# B204X.net
KiCad netlist of a schematic drawn in EAGLE
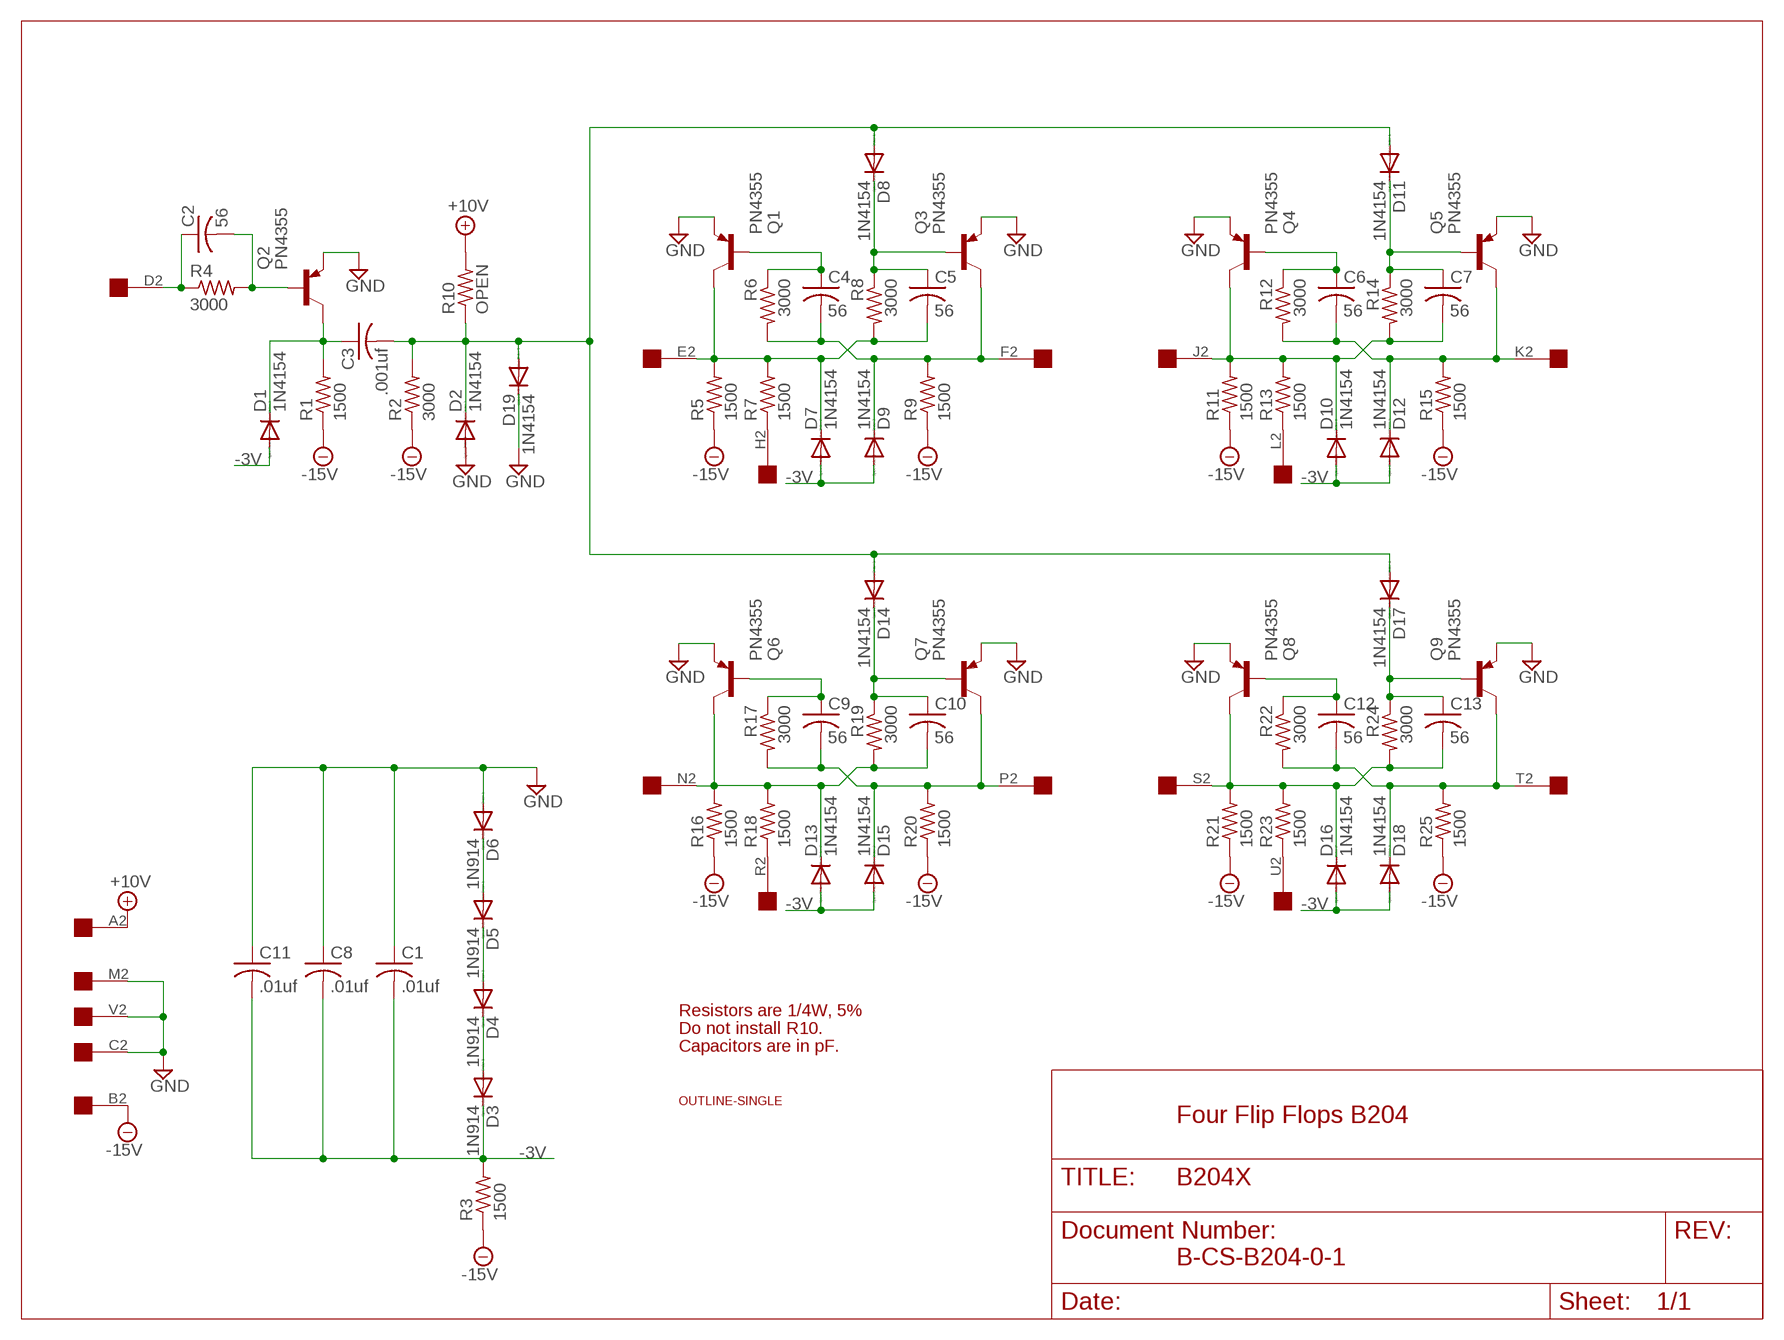
[diagram p0: schematic, sheet 1]

(export (version "E")
  (design (tool "Eeschema 10.0.6"))
  (components
    (comp (ref "C1")
      (value ".01uf")
      (footprint "eagle-import:C050-025X075")
      (libsource (lib "eagle-import") (part "C-US050-025X075"))
    )
    (comp (ref "C2")
      (value "56")
      (footprint "eagle-import:C075-032X103")
      (libsource (lib "eagle-import") (part "C-US075-032X103"))
    )
    (comp (ref "C3")
      (value ".001uf")
      (footprint "eagle-import:C050-025X075")
      (libsource (lib "eagle-import") (part "C-US050-025X075"))
    )
    (comp (ref "C4")
      (value "56")
      (footprint "eagle-import:C075-032X103")
      (libsource (lib "eagle-import") (part "C-US075-032X103"))
    )
    (comp (ref "C5")
      (value "56")
      (footprint "eagle-import:C075-032X103")
      (libsource (lib "eagle-import") (part "C-US075-032X103"))
    )
    (comp (ref "C6")
      (value "56")
      (footprint "eagle-import:C075-032X103")
      (libsource (lib "eagle-import") (part "C-US075-032X103"))
    )
    (comp (ref "C7")
      (value "56")
      (footprint "eagle-import:C075-032X103")
      (libsource (lib "eagle-import") (part "C-US075-032X103"))
    )
    (comp (ref "C8")
      (value ".01uf")
      (footprint "eagle-import:C050-025X075")
      (libsource (lib "eagle-import") (part "C-US050-025X075"))
    )
    (comp (ref "C9")
      (value "56")
      (footprint "eagle-import:C075-032X103")
      (libsource (lib "eagle-import") (part "C-US075-032X103"))
    )
    (comp (ref "C10")
      (value "56")
      (footprint "eagle-import:C075-032X103")
      (libsource (lib "eagle-import") (part "C-US075-032X103"))
    )
    (comp (ref "C11")
      (value ".01uf")
      (footprint "eagle-import:C050-025X075")
      (libsource (lib "eagle-import") (part "C-US050-025X075"))
    )
    (comp (ref "C12")
      (value "56")
      (footprint "eagle-import:C075-032X103")
      (libsource (lib "eagle-import") (part "C-US075-032X103"))
    )
    (comp (ref "C13")
      (value "56")
      (footprint "eagle-import:C075-032X103")
      (libsource (lib "eagle-import") (part "C-US075-032X103"))
    )
    (comp (ref "D1")
      (value "1N4154")
      (footprint "eagle-import:DO35-10")
      (libsource (lib "eagle-import") (part "1N4148DO35-10"))
    )
    (comp (ref "D2")
      (value "1N4154")
      (footprint "eagle-import:DO35-10")
      (libsource (lib "eagle-import") (part "1N4148DO35-10"))
    )
    (comp (ref "D3")
      (value "1N914")
      (footprint "eagle-import:DO35-10")
      (libsource (lib "eagle-import") (part "1N4148DO35-10"))
    )
    (comp (ref "D4")
      (value "1N914")
      (footprint "eagle-import:DO35-10")
      (libsource (lib "eagle-import") (part "1N4148DO35-10"))
    )
    (comp (ref "D5")
      (value "1N914")
      (footprint "eagle-import:DO35-10")
      (libsource (lib "eagle-import") (part "1N4148DO35-10"))
    )
    (comp (ref "D6")
      (value "1N914")
      (footprint "eagle-import:DO35-10")
      (libsource (lib "eagle-import") (part "1N4148DO35-10"))
    )
    (comp (ref "D7")
      (value "1N4154")
      (footprint "eagle-import:DO35-10")
      (libsource (lib "eagle-import") (part "1N4148DO35-10"))
    )
    (comp (ref "D8")
      (value "1N4154")
      (footprint "eagle-import:DO35-10")
      (libsource (lib "eagle-import") (part "1N4148DO35-10"))
    )
    (comp (ref "D9")
      (value "1N4154")
      (footprint "eagle-import:DO35-10")
      (libsource (lib "eagle-import") (part "1N4148DO35-10"))
    )
    (comp (ref "D10")
      (value "1N4154")
      (footprint "eagle-import:DO35-10")
      (libsource (lib "eagle-import") (part "1N4148DO35-10"))
    )
    (comp (ref "D11")
      (value "1N4154")
      (footprint "eagle-import:DO35-10")
      (libsource (lib "eagle-import") (part "1N4148DO35-10"))
    )
    (comp (ref "D12")
      (value "1N4154")
      (footprint "eagle-import:DO35-10")
      (libsource (lib "eagle-import") (part "1N4148DO35-10"))
    )
    (comp (ref "D13")
      (value "1N4154")
      (footprint "eagle-import:DO35-10")
      (libsource (lib "eagle-import") (part "1N4148DO35-10"))
    )
    (comp (ref "D14")
      (value "1N4154")
      (footprint "eagle-import:DO35-10")
      (libsource (lib "eagle-import") (part "1N4148DO35-10"))
    )
    (comp (ref "D15")
      (value "1N4154")
      (footprint "eagle-import:DO35-10")
      (libsource (lib "eagle-import") (part "1N4148DO35-10"))
    )
    (comp (ref "D16")
      (value "1N4154")
      (footprint "eagle-import:DO35-10")
      (libsource (lib "eagle-import") (part "1N4148DO35-10"))
    )
    (comp (ref "D17")
      (value "1N4154")
      (footprint "eagle-import:DO35-10")
      (libsource (lib "eagle-import") (part "1N4148DO35-10"))
    )
    (comp (ref "D18")
      (value "1N4154")
      (footprint "eagle-import:DO35-10")
      (libsource (lib "eagle-import") (part "1N4148DO35-10"))
    )
    (comp (ref "D19")
      (value "1N4154")
      (footprint "eagle-import:DO35-10")
      (libsource (lib "eagle-import") (part "1N4148DO35-10"))
    )
    (comp (ref "Q1")
      (value "PN4355")
      (footprint "eagle-import:TO39")
      (libsource (lib "eagle-import") (part "2N3637"))
    )
    (comp (ref "Q2")
      (value "PN4355")
      (footprint "eagle-import:TO39")
      (libsource (lib "eagle-import") (part "2N3637"))
    )
    (comp (ref "Q3")
      (value "PN4355")
      (footprint "eagle-import:TO39")
      (libsource (lib "eagle-import") (part "2N3637"))
    )
    (comp (ref "Q4")
      (value "PN4355")
      (footprint "eagle-import:TO39")
      (libsource (lib "eagle-import") (part "2N3637"))
    )
    (comp (ref "Q5")
      (value "PN4355")
      (footprint "eagle-import:TO39")
      (libsource (lib "eagle-import") (part "2N3637"))
    )
    (comp (ref "Q6")
      (value "PN4355")
      (footprint "eagle-import:TO39")
      (libsource (lib "eagle-import") (part "2N3637"))
    )
    (comp (ref "Q7")
      (value "PN4355")
      (footprint "eagle-import:TO39")
      (libsource (lib "eagle-import") (part "2N3637"))
    )
    (comp (ref "Q8")
      (value "PN4355")
      (footprint "eagle-import:TO39")
      (libsource (lib "eagle-import") (part "2N3637"))
    )
    (comp (ref "Q9")
      (value "PN4355")
      (footprint "eagle-import:TO39")
      (libsource (lib "eagle-import") (part "2N3637"))
    )
    (comp (ref "R1")
      (value "1500")
      (footprint "eagle-import:0207_10")
      (libsource (lib "eagle-import") (part "R-US_0207/10"))
    )
    (comp (ref "R2")
      (value "3000")
      (footprint "eagle-import:0207_10")
      (libsource (lib "eagle-import") (part "R-US_0207/10"))
    )
    (comp (ref "R3")
      (value "1500")
      (footprint "eagle-import:0207_10")
      (libsource (lib "eagle-import") (part "R-US_0207/10"))
    )
    (comp (ref "R4")
      (value "3000")
      (footprint "eagle-import:0207_10")
      (libsource (lib "eagle-import") (part "R-US_0207/10"))
    )
    (comp (ref "R5")
      (value "1500")
      (footprint "eagle-import:0207_10")
      (libsource (lib "eagle-import") (part "R-US_0207/10"))
    )
    (comp (ref "R6")
      (value "3000")
      (footprint "eagle-import:0207_10")
      (libsource (lib "eagle-import") (part "R-US_0207/10"))
    )
    (comp (ref "R7")
      (value "1500")
      (footprint "eagle-import:0207_10")
      (libsource (lib "eagle-import") (part "R-US_0207/10"))
    )
    (comp (ref "R8")
      (value "3000")
      (footprint "eagle-import:0207_10")
      (libsource (lib "eagle-import") (part "R-US_0207/10"))
    )
    (comp (ref "R9")
      (value "1500")
      (footprint "eagle-import:0207_10")
      (libsource (lib "eagle-import") (part "R-US_0207/10"))
    )
    (comp (ref "R10")
      (value "OPEN")
      (footprint "eagle-import:0207_10")
      (libsource (lib "eagle-import") (part "R-US_0207/10"))
    )
    (comp (ref "R11")
      (value "1500")
      (footprint "eagle-import:0207_10")
      (libsource (lib "eagle-import") (part "R-US_0207/10"))
    )
    (comp (ref "R12")
      (value "3000")
      (footprint "eagle-import:0207_10")
      (libsource (lib "eagle-import") (part "R-US_0207/10"))
    )
    (comp (ref "R13")
      (value "1500")
      (footprint "eagle-import:0207_10")
      (libsource (lib "eagle-import") (part "R-US_0207/10"))
    )
    (comp (ref "R14")
      (value "3000")
      (footprint "eagle-import:0207_10")
      (libsource (lib "eagle-import") (part "R-US_0207/10"))
    )
    (comp (ref "R15")
      (value "1500")
      (footprint "eagle-import:0207_10")
      (libsource (lib "eagle-import") (part "R-US_0207/10"))
    )
    (comp (ref "R16")
      (value "1500")
      (footprint "eagle-import:0207_10")
      (libsource (lib "eagle-import") (part "R-US_0207/10"))
    )
    (comp (ref "R17")
      (value "3000")
      (footprint "eagle-import:0207_10")
      (libsource (lib "eagle-import") (part "R-US_0207/10"))
    )
    (comp (ref "R18")
      (value "1500")
      (footprint "eagle-import:0207_10")
      (libsource (lib "eagle-import") (part "R-US_0207/10"))
    )
    (comp (ref "R19")
      (value "3000")
      (footprint "eagle-import:0207_10")
      (libsource (lib "eagle-import") (part "R-US_0207/10"))
    )
    (comp (ref "R20")
      (value "1500")
      (footprint "eagle-import:0207_10")
      (libsource (lib "eagle-import") (part "R-US_0207/10"))
    )
    (comp (ref "R21")
      (value "1500")
      (footprint "eagle-import:0207_10")
      (libsource (lib "eagle-import") (part "R-US_0207/10"))
    )
    (comp (ref "R22")
      (value "3000")
      (footprint "eagle-import:0207_10")
      (libsource (lib "eagle-import") (part "R-US_0207/10"))
    )
    (comp (ref "R23")
      (value "1500")
      (footprint "eagle-import:0207_10")
      (libsource (lib "eagle-import") (part "R-US_0207/10"))
    )
    (comp (ref "R24")
      (value "3000")
      (footprint "eagle-import:0207_10")
      (libsource (lib "eagle-import") (part "R-US_0207/10"))
    )
    (comp (ref "R25")
      (value "1500")
      (footprint "eagle-import:0207_10")
      (libsource (lib "eagle-import") (part "R-US_0207/10"))
    )
    (comp (ref "U$1")
      (value "OUTLINE-SINGLE")
      (footprint "eagle-import:SINGLE")
      (libsource (lib "eagle-import") (part "OUTLINE-SINGLE"))
    )
    (comp (ref "U$2")
      (value "EDGE-1")
      (footprint "eagle-import:EDGE-CON1")
      (libsource (lib "eagle-import") (part "EDGE-1"))
    )
  )
  (nets
    (net (code "1") (name "+10V") (class "Default")
      (node (ref "R10") (pin "2") (pinfunction "2_2") (pintype "passive"))
      (node (ref "U$2") (pin "A2") (pinfunction "1_A2") (pintype "bidirectional"))
    )
    (net (code "2") (name "-15V") (class "Default")
      (node (ref "R1") (pin "1") (pinfunction "1_1") (pintype "passive"))
      (node (ref "R11") (pin "1") (pinfunction "1_1") (pintype "passive"))
      (node (ref "R15") (pin "1") (pinfunction "1_1") (pintype "passive"))
      (node (ref "R16") (pin "1") (pinfunction "1_1") (pintype "passive"))
      (node (ref "R2") (pin "1") (pinfunction "1_1") (pintype "passive"))
      (node (ref "R20") (pin "1") (pinfunction "1_1") (pintype "passive"))
      (node (ref "R21") (pin "1") (pinfunction "1_1") (pintype "passive"))
      (node (ref "R25") (pin "1") (pinfunction "1_1") (pintype "passive"))
      (node (ref "R3") (pin "1") (pinfunction "1_1") (pintype "passive"))
      (node (ref "R5") (pin "1") (pinfunction "1_1") (pintype "passive"))
      (node (ref "R9") (pin "1") (pinfunction "1_1") (pintype "passive"))
      (node (ref "U$2") (pin "B2") (pinfunction "1_B2") (pintype "bidirectional"))
    )
    (net (code "3") (name "/-3V") (class "Default")
      (node (ref "C1") (pin "2") (pinfunction "2_2") (pintype "passive"))
      (node (ref "C11") (pin "2") (pinfunction "2_2") (pintype "passive"))
      (node (ref "C8") (pin "2") (pinfunction "2_2") (pintype "passive"))
      (node (ref "D1") (pin "A") (pinfunction "A_A") (pintype "passive"))
      (node (ref "D10") (pin "A") (pinfunction "A_A") (pintype "passive"))
      (node (ref "D12") (pin "A") (pinfunction "A_A") (pintype "passive"))
      (node (ref "D13") (pin "A") (pinfunction "A_A") (pintype "passive"))
      (node (ref "D15") (pin "A") (pinfunction "A_A") (pintype "passive"))
      (node (ref "D16") (pin "A") (pinfunction "A_A") (pintype "passive"))
      (node (ref "D18") (pin "A") (pinfunction "A_A") (pintype "passive"))
      (node (ref "D3") (pin "C") (pinfunction "C_C") (pintype "passive"))
      (node (ref "D7") (pin "A") (pinfunction "A_A") (pintype "passive"))
      (node (ref "D9") (pin "A") (pinfunction "A_A") (pintype "passive"))
      (node (ref "R3") (pin "2") (pinfunction "2_2") (pintype "passive"))
    )
    (net (code "4") (name "GND") (class "Default")
      (node (ref "C1") (pin "1") (pinfunction "1_1") (pintype "passive"))
      (node (ref "C11") (pin "1") (pinfunction "1_1") (pintype "passive"))
      (node (ref "C8") (pin "1") (pinfunction "1_1") (pintype "passive"))
      (node (ref "D19") (pin "C") (pinfunction "C_C") (pintype "passive"))
      (node (ref "D2") (pin "A") (pinfunction "A_A") (pintype "passive"))
      (node (ref "D6") (pin "A") (pinfunction "A_A") (pintype "passive"))
      (node (ref "Q1") (pin "1") (pinfunction "E_1") (pintype "passive"))
      (node (ref "Q2") (pin "1") (pinfunction "E_1") (pintype "passive"))
      (node (ref "Q3") (pin "1") (pinfunction "E_1") (pintype "passive"))
      (node (ref "Q4") (pin "1") (pinfunction "E_1") (pintype "passive"))
      (node (ref "Q5") (pin "1") (pinfunction "E_1") (pintype "passive"))
      (node (ref "Q6") (pin "1") (pinfunction "E_1") (pintype "passive"))
      (node (ref "Q7") (pin "1") (pinfunction "E_1") (pintype "passive"))
      (node (ref "Q8") (pin "1") (pinfunction "E_1") (pintype "passive"))
      (node (ref "Q9") (pin "1") (pinfunction "E_1") (pintype "passive"))
      (node (ref "U$2") (pin "C2") (pinfunction "1_C2") (pintype "bidirectional"))
      (node (ref "U$2") (pin "M2") (pinfunction "1_M2") (pintype "bidirectional"))
      (node (ref "U$2") (pin "V2") (pinfunction "1_V2") (pintype "bidirectional"))
    )
    (net (code "5") (name "Net-(C3-Pad2)") (class "Default")
      (node (ref "C3") (pin "2") (pinfunction "2_2") (pintype "passive"))
      (node (ref "D11") (pin "A") (pinfunction "A_A") (pintype "passive"))
      (node (ref "D14") (pin "A") (pinfunction "A_A") (pintype "passive"))
      (node (ref "D17") (pin "A") (pinfunction "A_A") (pintype "passive"))
      (node (ref "D19") (pin "A") (pinfunction "A_A") (pintype "passive"))
      (node (ref "D2") (pin "C") (pinfunction "C_C") (pintype "passive"))
      (node (ref "D8") (pin "A") (pinfunction "A_A") (pintype "passive"))
      (node (ref "R10") (pin "1") (pinfunction "1_1") (pintype "passive"))
      (node (ref "R2") (pin "2") (pinfunction "2_2") (pintype "passive"))
    )
    (net (code "6") (name "Net-(D3-PadA)") (class "Default")
      (node (ref "D3") (pin "A") (pinfunction "A_A") (pintype "passive"))
      (node (ref "D4") (pin "C") (pinfunction "C_C") (pintype "passive"))
    )
    (net (code "7") (name "Net-(D4-PadA)") (class "Default")
      (node (ref "D4") (pin "A") (pinfunction "A_A") (pintype "passive"))
      (node (ref "D5") (pin "C") (pinfunction "C_C") (pintype "passive"))
    )
    (net (code "8") (name "Net-(D5-PadA)") (class "Default")
      (node (ref "D5") (pin "A") (pinfunction "A_A") (pintype "passive"))
      (node (ref "D6") (pin "C") (pinfunction "C_C") (pintype "passive"))
    )
    (net (code "9") (name "Net-(Q1-B)") (class "Default")
      (node (ref "C4") (pin "1") (pinfunction "1_1") (pintype "passive"))
      (node (ref "Q1") (pin "2") (pinfunction "B_2") (pintype "passive"))
      (node (ref "R6") (pin "1") (pinfunction "1_1") (pintype "passive"))
    )
    (net (code "10") (name "Net-(Q1-C)") (class "Default")
      (node (ref "C5") (pin "2") (pinfunction "2_2") (pintype "passive"))
      (node (ref "D7") (pin "C") (pinfunction "C_C") (pintype "passive"))
      (node (ref "Q1") (pin "3") (pinfunction "C_3") (pintype "passive"))
      (node (ref "R5") (pin "2") (pinfunction "2_2") (pintype "passive"))
      (node (ref "R7") (pin "2") (pinfunction "2_2") (pintype "passive"))
      (node (ref "R8") (pin "2") (pinfunction "2_2") (pintype "passive"))
      (node (ref "U$2") (pin "E2") (pinfunction "1_E2") (pintype "bidirectional"))
    )
    (net (code "11") (name "Net-(Q2-B)") (class "Default")
      (node (ref "C2") (pin "2") (pinfunction "2_2") (pintype "passive"))
      (node (ref "Q2") (pin "2") (pinfunction "B_2") (pintype "passive"))
      (node (ref "R4") (pin "2") (pinfunction "2_2") (pintype "passive"))
    )
    (net (code "12") (name "Net-(Q2-C)") (class "Default")
      (node (ref "C3") (pin "1") (pinfunction "1_1") (pintype "passive"))
      (node (ref "D1") (pin "C") (pinfunction "C_C") (pintype "passive"))
      (node (ref "Q2") (pin "3") (pinfunction "C_3") (pintype "passive"))
      (node (ref "R1") (pin "2") (pinfunction "2_2") (pintype "passive"))
    )
    (net (code "13") (name "Net-(Q3-B)") (class "Default")
      (node (ref "C5") (pin "1") (pinfunction "1_1") (pintype "passive"))
      (node (ref "D8") (pin "C") (pinfunction "C_C") (pintype "passive"))
      (node (ref "Q3") (pin "2") (pinfunction "B_2") (pintype "passive"))
      (node (ref "R8") (pin "1") (pinfunction "1_1") (pintype "passive"))
    )
    (net (code "14") (name "Net-(Q3-C)") (class "Default")
      (node (ref "C4") (pin "2") (pinfunction "2_2") (pintype "passive"))
      (node (ref "D9") (pin "C") (pinfunction "C_C") (pintype "passive"))
      (node (ref "Q3") (pin "3") (pinfunction "C_3") (pintype "passive"))
      (node (ref "R6") (pin "2") (pinfunction "2_2") (pintype "passive"))
      (node (ref "R9") (pin "2") (pinfunction "2_2") (pintype "passive"))
      (node (ref "U$2") (pin "F2") (pinfunction "1_F2") (pintype "bidirectional"))
    )
    (net (code "15") (name "Net-(Q4-B)") (class "Default")
      (node (ref "C6") (pin "1") (pinfunction "1_1") (pintype "passive"))
      (node (ref "Q4") (pin "2") (pinfunction "B_2") (pintype "passive"))
      (node (ref "R12") (pin "1") (pinfunction "1_1") (pintype "passive"))
    )
    (net (code "16") (name "Net-(Q4-C)") (class "Default")
      (node (ref "C7") (pin "2") (pinfunction "2_2") (pintype "passive"))
      (node (ref "D10") (pin "C") (pinfunction "C_C") (pintype "passive"))
      (node (ref "Q4") (pin "3") (pinfunction "C_3") (pintype "passive"))
      (node (ref "R11") (pin "2") (pinfunction "2_2") (pintype "passive"))
      (node (ref "R13") (pin "2") (pinfunction "2_2") (pintype "passive"))
      (node (ref "R14") (pin "2") (pinfunction "2_2") (pintype "passive"))
      (node (ref "U$2") (pin "J2") (pinfunction "1_J2") (pintype "bidirectional"))
    )
    (net (code "17") (name "Net-(Q5-B)") (class "Default")
      (node (ref "C7") (pin "1") (pinfunction "1_1") (pintype "passive"))
      (node (ref "D11") (pin "C") (pinfunction "C_C") (pintype "passive"))
      (node (ref "Q5") (pin "2") (pinfunction "B_2") (pintype "passive"))
      (node (ref "R14") (pin "1") (pinfunction "1_1") (pintype "passive"))
    )
    (net (code "18") (name "Net-(Q5-C)") (class "Default")
      (node (ref "C6") (pin "2") (pinfunction "2_2") (pintype "passive"))
      (node (ref "D12") (pin "C") (pinfunction "C_C") (pintype "passive"))
      (node (ref "Q5") (pin "3") (pinfunction "C_3") (pintype "passive"))
      (node (ref "R12") (pin "2") (pinfunction "2_2") (pintype "passive"))
      (node (ref "R15") (pin "2") (pinfunction "2_2") (pintype "passive"))
      (node (ref "U$2") (pin "K2") (pinfunction "1_K2") (pintype "bidirectional"))
    )
    (net (code "19") (name "Net-(Q6-B)") (class "Default")
      (node (ref "C9") (pin "1") (pinfunction "1_1") (pintype "passive"))
      (node (ref "Q6") (pin "2") (pinfunction "B_2") (pintype "passive"))
      (node (ref "R17") (pin "1") (pinfunction "1_1") (pintype "passive"))
    )
    (net (code "20") (name "Net-(Q6-C)") (class "Default")
      (node (ref "C10") (pin "2") (pinfunction "2_2") (pintype "passive"))
      (node (ref "D13") (pin "C") (pinfunction "C_C") (pintype "passive"))
      (node (ref "Q6") (pin "3") (pinfunction "C_3") (pintype "passive"))
      (node (ref "R16") (pin "2") (pinfunction "2_2") (pintype "passive"))
      (node (ref "R18") (pin "2") (pinfunction "2_2") (pintype "passive"))
      (node (ref "R19") (pin "2") (pinfunction "2_2") (pintype "passive"))
      (node (ref "U$2") (pin "N2") (pinfunction "1_N2") (pintype "bidirectional"))
    )
    (net (code "21") (name "Net-(Q7-B)") (class "Default")
      (node (ref "C10") (pin "1") (pinfunction "1_1") (pintype "passive"))
      (node (ref "D14") (pin "C") (pinfunction "C_C") (pintype "passive"))
      (node (ref "Q7") (pin "2") (pinfunction "B_2") (pintype "passive"))
      (node (ref "R19") (pin "1") (pinfunction "1_1") (pintype "passive"))
    )
    (net (code "22") (name "Net-(Q7-C)") (class "Default")
      (node (ref "C9") (pin "2") (pinfunction "2_2") (pintype "passive"))
      (node (ref "D15") (pin "C") (pinfunction "C_C") (pintype "passive"))
      (node (ref "Q7") (pin "3") (pinfunction "C_3") (pintype "passive"))
      (node (ref "R17") (pin "2") (pinfunction "2_2") (pintype "passive"))
      (node (ref "R20") (pin "2") (pinfunction "2_2") (pintype "passive"))
      (node (ref "U$2") (pin "P2") (pinfunction "1_P2") (pintype "bidirectional"))
    )
    (net (code "23") (name "Net-(Q8-B)") (class "Default")
      (node (ref "C12") (pin "1") (pinfunction "1_1") (pintype "passive"))
      (node (ref "Q8") (pin "2") (pinfunction "B_2") (pintype "passive"))
      (node (ref "R22") (pin "1") (pinfunction "1_1") (pintype "passive"))
    )
    (net (code "24") (name "Net-(Q8-C)") (class "Default")
      (node (ref "C13") (pin "2") (pinfunction "2_2") (pintype "passive"))
      (node (ref "D16") (pin "C") (pinfunction "C_C") (pintype "passive"))
      (node (ref "Q8") (pin "3") (pinfunction "C_3") (pintype "passive"))
      (node (ref "R21") (pin "2") (pinfunction "2_2") (pintype "passive"))
      (node (ref "R23") (pin "2") (pinfunction "2_2") (pintype "passive"))
      (node (ref "R24") (pin "2") (pinfunction "2_2") (pintype "passive"))
      (node (ref "U$2") (pin "S2") (pinfunction "1_S2") (pintype "bidirectional"))
    )
    (net (code "25") (name "Net-(Q9-B)") (class "Default")
      (node (ref "C13") (pin "1") (pinfunction "1_1") (pintype "passive"))
      (node (ref "D17") (pin "C") (pinfunction "C_C") (pintype "passive"))
      (node (ref "Q9") (pin "2") (pinfunction "B_2") (pintype "passive"))
      (node (ref "R24") (pin "1") (pinfunction "1_1") (pintype "passive"))
    )
    (net (code "26") (name "Net-(Q9-C)") (class "Default")
      (node (ref "C12") (pin "2") (pinfunction "2_2") (pintype "passive"))
      (node (ref "D18") (pin "C") (pinfunction "C_C") (pintype "passive"))
      (node (ref "Q9") (pin "3") (pinfunction "C_3") (pintype "passive"))
      (node (ref "R22") (pin "2") (pinfunction "2_2") (pintype "passive"))
      (node (ref "R25") (pin "2") (pinfunction "2_2") (pintype "passive"))
      (node (ref "U$2") (pin "T2") (pinfunction "1_T2") (pintype "bidirectional"))
    )
    (net (code "27") (name "Net-(U$2D-1)") (class "Default")
      (node (ref "C2") (pin "1") (pinfunction "1_1") (pintype "passive"))
      (node (ref "R4") (pin "1") (pinfunction "1_1") (pintype "passive"))
      (node (ref "U$2") (pin "D2") (pinfunction "1_D2") (pintype "bidirectional"))
    )
    (net (code "28") (name "Net-(U$2G-1)") (class "Default")
      (node (ref "R7") (pin "1") (pinfunction "1_1") (pintype "passive"))
      (node (ref "U$2") (pin "H2") (pinfunction "1_H2") (pintype "bidirectional"))
    )
    (net (code "29") (name "Net-(U$2J-1)") (class "Default")
      (node (ref "R13") (pin "1") (pinfunction "1_1") (pintype "passive"))
      (node (ref "U$2") (pin "L2") (pinfunction "1_L2") (pintype "bidirectional"))
    )
    (net (code "30") (name "Net-(U$2N-1)") (class "Default")
      (node (ref "R18") (pin "1") (pinfunction "1_1") (pintype "passive"))
      (node (ref "U$2") (pin "R2") (pinfunction "1_R2") (pintype "bidirectional"))
    )
    (net (code "31") (name "Net-(U$2Q-1)") (class "Default")
      (node (ref "R23") (pin "1") (pinfunction "1_1") (pintype "passive"))
      (node (ref "U$2") (pin "U2") (pinfunction "1_U2") (pintype "bidirectional"))
    )
  )
)
